# Sendeeinheit.net
KiCad netlist of a schematic drawn in EAGLE
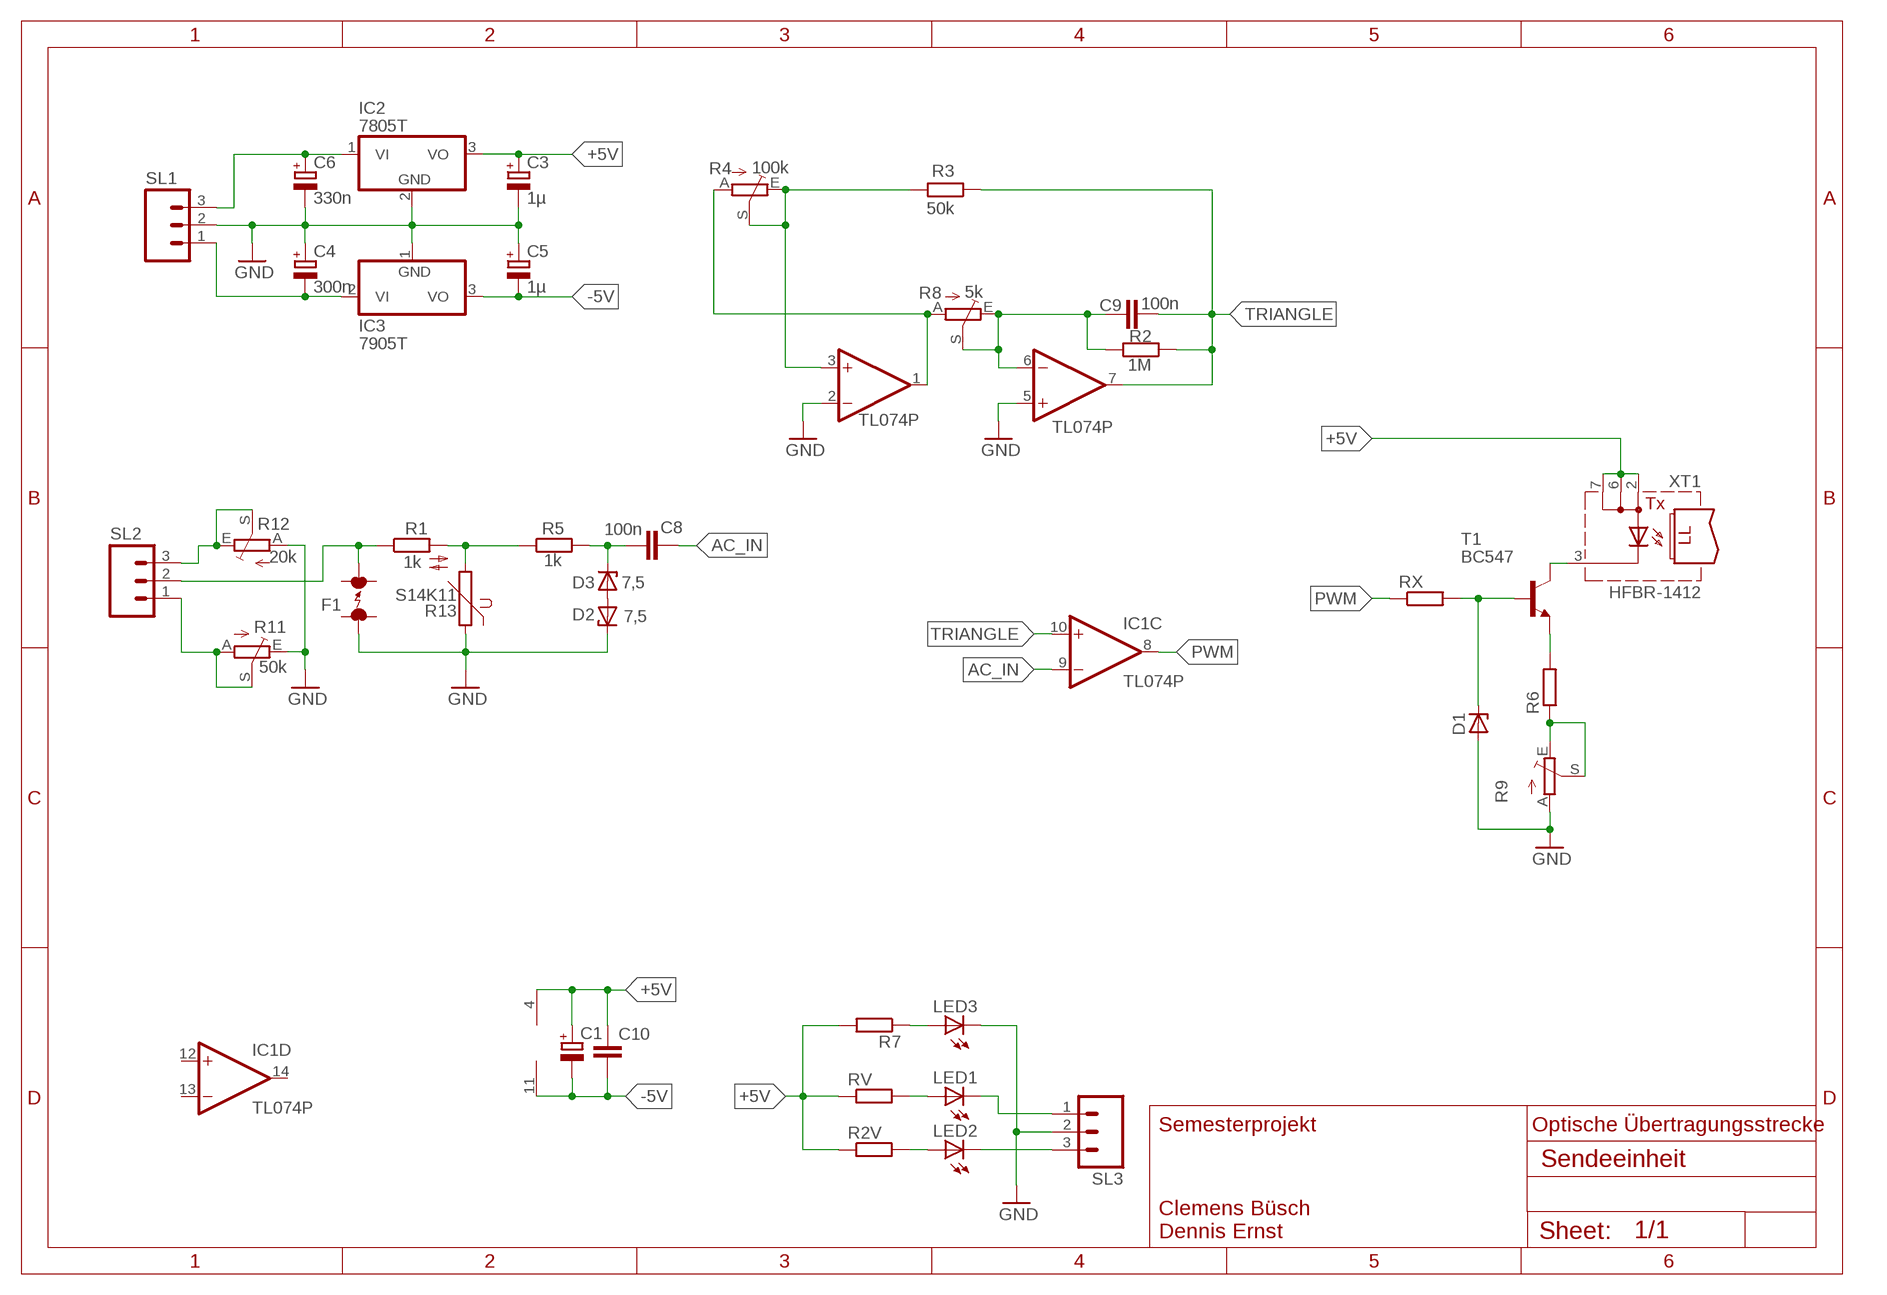
[diagram p0: schematic, sheet 1]

(export (version "E")
  (design (tool "Eeschema 10.0.6"))
  (components
    (comp (ref "C1")
      (value "CPOL-EUE5-10.5")
      (footprint "eagle-import:E5-10,5")
      (libsource (lib "eagle-import") (part "CPOL-EUE5-10.5"))
    )
    (comp (ref "C3")
      (value "1µ")
      (footprint "eagle-import:E5-10,5")
      (libsource (lib "eagle-import") (part "CPOL-EUE5-10.5"))
    )
    (comp (ref "C4")
      (value "300n")
      (footprint "eagle-import:E5-10,5")
      (libsource (lib "eagle-import") (part "CPOL-EUE5-10.5"))
    )
    (comp (ref "C5")
      (value "1µ")
      (footprint "eagle-import:E5-10,5")
      (libsource (lib "eagle-import") (part "CPOL-EUE5-10.5"))
    )
    (comp (ref "C6")
      (value "330n")
      (footprint "eagle-import:E5-10,5")
      (libsource (lib "eagle-import") (part "CPOL-EUE5-10.5"))
    )
    (comp (ref "C8")
      (value "100n")
      (footprint "eagle-import:C050-024X044")
      (libsource (lib "eagle-import") (part "C-EU050-024X044"))
    )
    (comp (ref "C9")
      (value "100n")
      (footprint "eagle-import:C050-024X044")
      (libsource (lib "eagle-import") (part "C-EU050-024X044"))
    )
    (comp (ref "C10")
      (value "C-EU050-024X044")
      (footprint "eagle-import:C050-024X044")
      (libsource (lib "eagle-import") (part "C-EU050-024X044"))
    )
    (comp (ref "D1")
      (value "ZENER-DIODEDO35Z10")
      (footprint "eagle-import:DO35Z10")
      (libsource (lib "eagle-import") (part "ZENER-DIODEDO35Z10"))
    )
    (comp (ref "D2")
      (value "7,5")
      (footprint "eagle-import:DO35Z10")
      (libsource (lib "eagle-import") (part "ZENER-DIODEDO35Z10"))
    )
    (comp (ref "D3")
      (value "7,5")
      (footprint "eagle-import:DO35Z10")
      (libsource (lib "eagle-import") (part "ZENER-DIODEDO35Z10"))
    )
    (comp (ref "F1")
      (value "ARRESTER")
      (footprint "eagle-import:EPCOS_N81")
      (libsource (lib "eagle-import") (part "ARRESTER"))
    )
    (comp (ref "IC1")
      (value "TL074P")
      (footprint "eagle-import:DIL14")
      (libsource (lib "eagle-import") (part "TL074P"))
    )
    (comp (ref "IC2")
      (value "7805T")
      (footprint "eagle-import:TO220H")
      (libsource (lib "eagle-import") (part "78T05"))
    )
    (comp (ref "IC3")
      (value "7905T")
      (footprint "eagle-import:TO220H")
      (libsource (lib "eagle-import") (part "79T08"))
    )
    (comp (ref "LED1")
      (value "LED3MM")
      (footprint "eagle-import:LED3MM")
      (libsource (lib "eagle-import") (part "LED3MM"))
    )
    (comp (ref "LED2")
      (value "LED3MM")
      (footprint "eagle-import:LED3MM")
      (libsource (lib "eagle-import") (part "LED3MM"))
    )
    (comp (ref "LED3")
      (value "LED3MM")
      (footprint "eagle-import:LED3MM")
      (libsource (lib "eagle-import") (part "LED3MM"))
    )
    (comp (ref "R1")
      (value "1k")
      (footprint "eagle-import:0207_10")
      (libsource (lib "eagle-import") (part "R-EU_0207/10"))
    )
    (comp (ref "R2")
      (value "1M")
      (footprint "eagle-import:0207_10")
      (libsource (lib "eagle-import") (part "R-EU_0207/10"))
    )
    (comp (ref "R2V")
      (value "R-EU_0207/10")
      (footprint "eagle-import:0207_10")
      (libsource (lib "eagle-import") (part "R-EU_0207/10"))
    )
    (comp (ref "R3")
      (value "50k")
      (footprint "eagle-import:0207_10")
      (libsource (lib "eagle-import") (part "R-EU_0207/10"))
    )
    (comp (ref "R4")
      (value "100k")
      (footprint "eagle-import:RJ9W")
      (libsource (lib "eagle-import") (part "TRIM_EU-RJ9W"))
    )
    (comp (ref "R5")
      (value "1k")
      (footprint "eagle-import:0207_10")
      (libsource (lib "eagle-import") (part "R-EU_0207/10"))
    )
    (comp (ref "R6")
      (value "R-EU_0207/10")
      (footprint "eagle-import:0207_10")
      (libsource (lib "eagle-import") (part "R-EU_0207/10"))
    )
    (comp (ref "R7")
      (value "R-EU_0207/10")
      (footprint "eagle-import:0207_10")
      (libsource (lib "eagle-import") (part "R-EU_0207/10"))
    )
    (comp (ref "R8")
      (value "5k")
      (footprint "eagle-import:RJ9W")
      (libsource (lib "eagle-import") (part "TRIM_EU-RJ9W"))
    )
    (comp (ref "R9")
      (value "TRIM_EU-RJ9W")
      (footprint "eagle-import:RJ9W")
      (libsource (lib "eagle-import") (part "TRIM_EU-RJ9W"))
    )
    (comp (ref "R11")
      (value "50k")
      (footprint "eagle-import:RJ9W")
      (libsource (lib "eagle-import") (part "TRIM_EU-RJ9W"))
    )
    (comp (ref "R12")
      (value "20k")
      (footprint "eagle-import:RJ9W")
      (libsource (lib "eagle-import") (part "TRIM_EU-RJ9W"))
    )
    (comp (ref "R13")
      (value "S14K11")
      (footprint "eagle-import:S14K11")
      (libsource (lib "eagle-import") (part "S14K11"))
    )
    (comp (ref "RV")
      (value "R-EU_0207/10")
      (footprint "eagle-import:0207_10")
      (libsource (lib "eagle-import") (part "R-EU_0207/10"))
    )
    (comp (ref "RX")
      (value "R-EU_0207/10")
      (footprint "eagle-import:0207_10")
      (libsource (lib "eagle-import") (part "R-EU_0207/10"))
    )
    (comp (ref "SL1")
      (value "M03")
      (footprint "eagle-import:03P")
      (libsource (lib "eagle-import") (part "M03"))
    )
    (comp (ref "SL2")
      (value "M03")
      (footprint "eagle-import:03P")
      (libsource (lib "eagle-import") (part "M03"))
    )
    (comp (ref "SL3")
      (value "M03")
      (footprint "eagle-import:03P")
      (libsource (lib "eagle-import") (part "M03"))
    )
    (comp (ref "T1")
      (value "BC547")
      (footprint "eagle-import:TO92")
      (libsource (lib "eagle-import") (part "BC547"))
    )
    (comp (ref "XT1")
      (value "HFBR-1412")
      (footprint "eagle-import:HFBR-X41X")
      (fields (field (name "MF") "AGILENT TECHNOLOGIES"))
      (libsource (lib "eagle-import") (part "HFBR-1412"))
    )
  )
  (nets
    (net (code "1") (name "+5V") (class "Default")
      (node (ref "C1") (pin "+") (pinfunction "+_+") (pintype "passive"))
      (node (ref "C10") (pin "1") (pinfunction "1_1") (pintype "passive"))
      (node (ref "C3") (pin "+") (pinfunction "+_+") (pintype "passive"))
      (node (ref "IC1") (pin "4") (pinfunction "V+_4") (pintype "power_in"))
      (node (ref "IC2") (pin "3") (pinfunction "VO_3") (pintype "passive"))
      (node (ref "R2V") (pin "1") (pinfunction "1_1") (pintype "passive"))
      (node (ref "R7") (pin "2") (pinfunction "2_2") (pintype "passive"))
      (node (ref "RV") (pin "1") (pinfunction "1_1") (pintype "passive"))
      (node (ref "XT1") (pin "2") (pinfunction "A_2") (pintype "passive"))
      (node (ref "XT1") (pin "6") (pinfunction "A1_6") (pintype "passive"))
      (node (ref "XT1") (pin "7") (pinfunction "A2_7") (pintype "passive"))
    )
    (net (code "2") (name "-5V") (class "Default")
      (node (ref "C1") (pin "-") (pinfunction "-_-") (pintype "passive"))
      (node (ref "C10") (pin "2") (pinfunction "2_2") (pintype "passive"))
      (node (ref "C5") (pin "-") (pinfunction "-_-") (pintype "passive"))
      (node (ref "IC1") (pin "11") (pinfunction "V-_11") (pintype "power_in"))
      (node (ref "IC3") (pin "3") (pinfunction "VO_3") (pintype "passive"))
    )
    (net (code "3") (name "AC_IN") (class "Default")
      (node (ref "C8") (pin "2") (pinfunction "2_2") (pintype "passive"))
      (node (ref "IC1") (pin "9") (pinfunction "-IN_9") (pintype "input"))
    )
    (net (code "4") (name "GND") (class "Default")
      (node (ref "C3") (pin "-") (pinfunction "-_-") (pintype "passive"))
      (node (ref "C4") (pin "+") (pinfunction "+_+") (pintype "passive"))
      (node (ref "C5") (pin "+") (pinfunction "+_+") (pintype "passive"))
      (node (ref "C6") (pin "-") (pinfunction "-_-") (pintype "passive"))
      (node (ref "D1") (pin "A") (pinfunction "A_A") (pintype "passive"))
      (node (ref "D2") (pin "C") (pinfunction "C_C") (pintype "passive"))
      (node (ref "F1") (pin "1") (pinfunction "1_1") (pintype "passive"))
      (node (ref "IC1") (pin "2") (pinfunction "-IN_2") (pintype "input"))
      (node (ref "IC1") (pin "5") (pinfunction "+IN_5") (pintype "input"))
      (node (ref "IC2") (pin "2") (pinfunction "GND_2") (pintype "passive"))
      (node (ref "IC3") (pin "1") (pinfunction "GND_1") (pintype "passive"))
      (node (ref "LED3") (pin "K") (pinfunction "C_K") (pintype "passive"))
      (node (ref "R11") (pin "E") (pinfunction "E_E") (pintype "passive"))
      (node (ref "R12") (pin "A") (pinfunction "A_A") (pintype "passive"))
      (node (ref "R13") (pin "1") (pinfunction "1_1") (pintype "passive"))
      (node (ref "R9") (pin "A") (pinfunction "A_A") (pintype "passive"))
      (node (ref "SL1") (pin "2") (pinfunction "2_2") (pintype "passive"))
      (node (ref "SL3") (pin "2") (pinfunction "2_2") (pintype "passive"))
    )
    (net (code "5") (name "Net-(C8-Pad1)") (class "Default")
      (node (ref "C8") (pin "1") (pinfunction "1_1") (pintype "passive"))
      (node (ref "D3") (pin "C") (pinfunction "C_C") (pintype "passive"))
      (node (ref "R5") (pin "2") (pinfunction "2_2") (pintype "passive"))
    )
    (net (code "6") (name "Net-(D2-PadA)") (class "Default")
      (node (ref "D2") (pin "A") (pinfunction "A_A") (pintype "passive"))
      (node (ref "D3") (pin "A") (pinfunction "A_A") (pintype "passive"))
    )
    (net (code "7") (name "Net-(F1-Pad2)") (class "Default")
      (node (ref "F1") (pin "2") (pinfunction "2_2") (pintype "passive"))
      (node (ref "R1") (pin "1") (pinfunction "1_1") (pintype "passive"))
      (node (ref "SL2") (pin "2") (pinfunction "2_2") (pintype "passive"))
    )
    (net (code "8") (name "Net-(IC1A-+IN)") (class "Default")
      (node (ref "IC1") (pin "3") (pinfunction "+IN_3") (pintype "input"))
      (node (ref "R3") (pin "2") (pinfunction "2_2") (pintype "passive"))
      (node (ref "R4") (pin "E") (pinfunction "E_E") (pintype "passive"))
      (node (ref "R4") (pin "S") (pinfunction "S_S") (pintype "passive"))
    )
    (net (code "9") (name "Net-(IC1A-OUT)") (class "Default")
      (node (ref "IC1") (pin "1") (pinfunction "OUT_1") (pintype "output"))
      (node (ref "R4") (pin "A") (pinfunction "A_A") (pintype "passive"))
      (node (ref "R8") (pin "A") (pinfunction "A_A") (pintype "passive"))
    )
    (net (code "10") (name "Net-(IC1B--IN)") (class "Default")
      (node (ref "C9") (pin "2") (pinfunction "2_2") (pintype "passive"))
      (node (ref "IC1") (pin "6") (pinfunction "-IN_6") (pintype "input"))
      (node (ref "R2") (pin "2") (pinfunction "2_2") (pintype "passive"))
      (node (ref "R8") (pin "E") (pinfunction "E_E") (pintype "passive"))
      (node (ref "R8") (pin "S") (pinfunction "S_S") (pintype "passive"))
    )
    (net (code "11") (name "Net-(IC2-VI)") (class "Default")
      (node (ref "C6") (pin "+") (pinfunction "+_+") (pintype "passive"))
      (node (ref "IC2") (pin "1") (pinfunction "VI_1") (pintype "input"))
      (node (ref "SL1") (pin "3") (pinfunction "3_3") (pintype "passive"))
    )
    (net (code "12") (name "Net-(IC3-VI)") (class "Default")
      (node (ref "C4") (pin "-") (pinfunction "-_-") (pintype "passive"))
      (node (ref "IC3") (pin "2") (pinfunction "VI_2") (pintype "input"))
      (node (ref "SL1") (pin "1") (pinfunction "1_1") (pintype "passive"))
    )
    (net (code "13") (name "Net-(LED1-C)") (class "Default")
      (node (ref "LED1") (pin "K") (pinfunction "C_K") (pintype "passive"))
      (node (ref "SL3") (pin "1") (pinfunction "1_1") (pintype "passive"))
    )
    (net (code "14") (name "Net-(LED1-PadA)") (class "Default")
      (node (ref "LED1") (pin "A") (pinfunction "A_A") (pintype "passive"))
      (node (ref "RV") (pin "2") (pinfunction "2_2") (pintype "passive"))
    )
    (net (code "15") (name "Net-(LED2-C)") (class "Default")
      (node (ref "LED2") (pin "K") (pinfunction "C_K") (pintype "passive"))
      (node (ref "SL3") (pin "3") (pinfunction "3_3") (pintype "passive"))
    )
    (net (code "16") (name "Net-(LED2-PadA)") (class "Default")
      (node (ref "LED2") (pin "A") (pinfunction "A_A") (pintype "passive"))
      (node (ref "R2V") (pin "2") (pinfunction "2_2") (pintype "passive"))
    )
    (net (code "17") (name "Net-(LED3-PadA)") (class "Default")
      (node (ref "LED3") (pin "A") (pinfunction "A_A") (pintype "passive"))
      (node (ref "R7") (pin "1") (pinfunction "1_1") (pintype "passive"))
    )
    (net (code "18") (name "Net-(R1-Pad2)") (class "Default")
      (node (ref "R1") (pin "2") (pinfunction "2_2") (pintype "passive"))
      (node (ref "R13") (pin "2") (pinfunction "2_2") (pintype "passive"))
      (node (ref "R5") (pin "1") (pinfunction "1_1") (pintype "passive"))
    )
    (net (code "19") (name "Net-(R6-Pad1)") (class "Default")
      (node (ref "R6") (pin "1") (pinfunction "1_1") (pintype "passive"))
      (node (ref "R9") (pin "E") (pinfunction "E_E") (pintype "passive"))
      (node (ref "R9") (pin "S") (pinfunction "S_S") (pintype "passive"))
    )
    (net (code "20") (name "Net-(R11-PadA)") (class "Default")
      (node (ref "R11") (pin "A") (pinfunction "A_A") (pintype "passive"))
      (node (ref "R11") (pin "S") (pinfunction "S_S") (pintype "passive"))
      (node (ref "SL2") (pin "1") (pinfunction "1_1") (pintype "passive"))
    )
    (net (code "21") (name "Net-(R12-PadE)") (class "Default")
      (node (ref "R12") (pin "E") (pinfunction "E_E") (pintype "passive"))
      (node (ref "R12") (pin "S") (pinfunction "S_S") (pintype "passive"))
      (node (ref "SL2") (pin "3") (pinfunction "3_3") (pintype "passive"))
    )
    (net (code "22") (name "Net-(T1-B)") (class "Default")
      (node (ref "D1") (pin "C") (pinfunction "C_C") (pintype "passive"))
      (node (ref "RX") (pin "2") (pinfunction "2_2") (pintype "passive"))
      (node (ref "T1") (pin "2") (pinfunction "B_2") (pintype "passive"))
    )
    (net (code "23") (name "Net-(T1-C)") (class "Default")
      (node (ref "T1") (pin "3") (pinfunction "C_3") (pintype "passive"))
      (node (ref "XT1") (pin "3") (pinfunction "C_3") (pintype "passive"))
    )
    (net (code "24") (name "Net-(T1-E)") (class "Default")
      (node (ref "R6") (pin "2") (pinfunction "2_2") (pintype "passive"))
      (node (ref "T1") (pin "1") (pinfunction "E_1") (pintype "passive"))
    )
    (net (code "25") (name "PWM") (class "Default")
      (node (ref "IC1") (pin "8") (pinfunction "OUT_8") (pintype "output"))
      (node (ref "RX") (pin "1") (pinfunction "1_1") (pintype "passive"))
    )
    (net (code "26") (name "TRIANGLE") (class "Default")
      (node (ref "C9") (pin "1") (pinfunction "1_1") (pintype "passive"))
      (node (ref "IC1") (pin "10") (pinfunction "+IN_10") (pintype "input"))
      (node (ref "IC1") (pin "7") (pinfunction "OUT_7") (pintype "output"))
      (node (ref "R2") (pin "1") (pinfunction "1_1") (pintype "passive"))
      (node (ref "R3") (pin "1") (pinfunction "1_1") (pintype "passive"))
    )
    (net (code "27") (name "unconnected-(IC1D-+IN-Pad12)") (class "Default")
      (node (ref "IC1") (pin "12") (pinfunction "+IN_12") (pintype "input"))
    )
    (net (code "28") (name "unconnected-(IC1D--IN-Pad13)") (class "Default")
      (node (ref "IC1") (pin "13") (pinfunction "-IN_13") (pintype "input"))
    )
    (net (code "29") (name "unconnected-(IC1D-OUT-Pad14)") (class "Default")
      (node (ref "IC1") (pin "14") (pinfunction "OUT_14") (pintype "output"))
    )
  )
)
